# C12_1_0.net
KiCad netlist of a schematic drawn in EAGLE
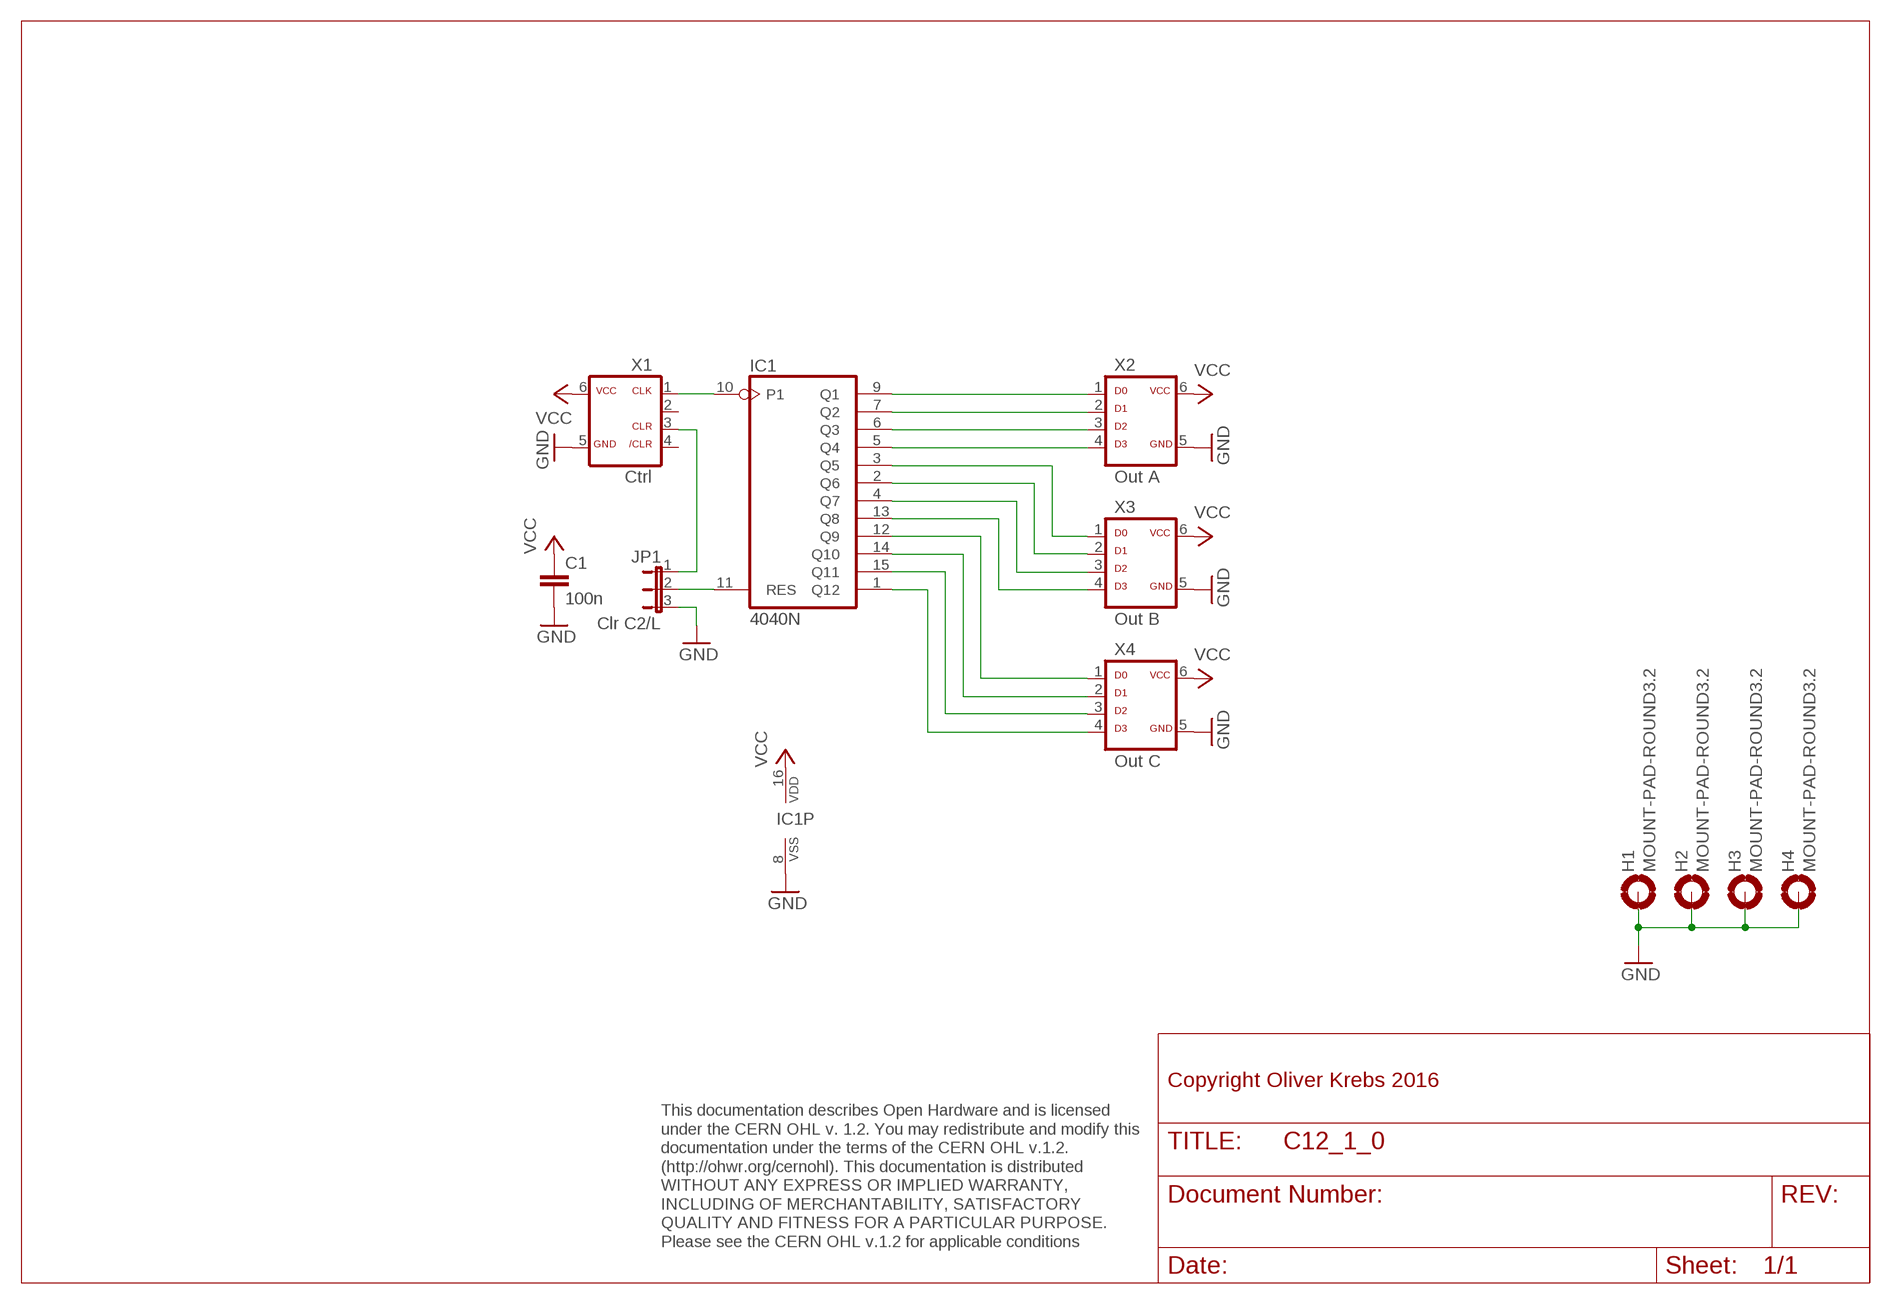
[diagram p0: schematic, sheet 1]

(export (version "E")
  (design (tool "Eeschema 10.0.6"))
  (components
    (comp (ref "C1")
      (value "100n")
      (footprint "eagle-import:C050-025X075")
      (libsource (lib "eagle-import") (part "C-EU050-025X075"))
    )
    (comp (ref "H1")
      (value "MOUNT-PAD-ROUND3.2")
      (footprint "eagle-import:3,2-PAD")
      (libsource (lib "eagle-import") (part "MOUNT-PAD-ROUND3.2"))
    )
    (comp (ref "H2")
      (value "MOUNT-PAD-ROUND3.2")
      (footprint "eagle-import:3,2-PAD")
      (libsource (lib "eagle-import") (part "MOUNT-PAD-ROUND3.2"))
    )
    (comp (ref "H3")
      (value "MOUNT-PAD-ROUND3.2")
      (footprint "eagle-import:3,2-PAD")
      (libsource (lib "eagle-import") (part "MOUNT-PAD-ROUND3.2"))
    )
    (comp (ref "H4")
      (value "MOUNT-PAD-ROUND3.2")
      (footprint "eagle-import:3,2-PAD")
      (libsource (lib "eagle-import") (part "MOUNT-PAD-ROUND3.2"))
    )
    (comp (ref "IC1")
      (value "4040N")
      (footprint "eagle-import:DIL16")
      (libsource (lib "eagle-import") (part "4040N"))
    )
    (comp (ref "JP1")
      (value "Clr C2/L")
      (footprint "eagle-import:JP2")
      (libsource (lib "eagle-import") (part "JP2E"))
    )
    (comp (ref "X1")
      (value "Ctrl")
      (footprint "eagle-import:ML-6")
      (libsource (lib "eagle-import") (part "ML6C"))
    )
    (comp (ref "X2")
      (value "Out A")
      (footprint "eagle-import:ML-6")
      (libsource (lib "eagle-import") (part "ML6D"))
    )
    (comp (ref "X3")
      (value "Out B")
      (footprint "eagle-import:ML-6")
      (libsource (lib "eagle-import") (part "ML6D"))
    )
    (comp (ref "X4")
      (value "Out C")
      (footprint "eagle-import:ML-6")
      (libsource (lib "eagle-import") (part "ML6D"))
    )
  )
  (nets
    (net (code "1") (name "GND") (class "Default")
      (node (ref "C1") (pin "2") (pinfunction "2_2") (pintype "passive"))
      (node (ref "H1") (pin "B3,2") (pinfunction "MOUNT_B3,2") (pintype "passive"))
      (node (ref "H2") (pin "B3,2") (pinfunction "MOUNT_B3,2") (pintype "passive"))
      (node (ref "H3") (pin "B3,2") (pinfunction "MOUNT_B3,2") (pintype "passive"))
      (node (ref "H4") (pin "B3,2") (pinfunction "MOUNT_B3,2") (pintype "passive"))
      (node (ref "IC1") (pin "8") (pinfunction "VSS_8") (pintype "power_in"))
      (node (ref "JP1") (pin "3") (pinfunction "3_3") (pintype "passive"))
      (node (ref "X1") (pin "5") (pinfunction "5_5") (pintype "passive"))
      (node (ref "X2") (pin "5") (pinfunction "5_5") (pintype "passive"))
      (node (ref "X3") (pin "5") (pinfunction "5_5") (pintype "passive"))
      (node (ref "X4") (pin "5") (pinfunction "5_5") (pintype "passive"))
    )
    (net (code "2") (name "Net-(IC1A-P1)") (class "Default")
      (node (ref "IC1") (pin "10") (pinfunction "P1_10") (pintype "input"))
      (node (ref "X1") (pin "1") (pinfunction "1_1") (pintype "passive"))
    )
    (net (code "3") (name "Net-(IC1A-Q1)") (class "Default")
      (node (ref "IC1") (pin "9") (pinfunction "Q1_9") (pintype "output"))
      (node (ref "X2") (pin "1") (pinfunction "1_1") (pintype "passive"))
    )
    (net (code "4") (name "Net-(IC1A-Q2)") (class "Default")
      (node (ref "IC1") (pin "7") (pinfunction "Q2_7") (pintype "output"))
      (node (ref "X2") (pin "2") (pinfunction "2_2") (pintype "passive"))
    )
    (net (code "5") (name "Net-(IC1A-Q3)") (class "Default")
      (node (ref "IC1") (pin "6") (pinfunction "Q3_6") (pintype "output"))
      (node (ref "X2") (pin "3") (pinfunction "3_3") (pintype "passive"))
    )
    (net (code "6") (name "Net-(IC1A-Q4)") (class "Default")
      (node (ref "IC1") (pin "5") (pinfunction "Q4_5") (pintype "output"))
      (node (ref "X2") (pin "4") (pinfunction "4_4") (pintype "passive"))
    )
    (net (code "7") (name "Net-(IC1A-Q5)") (class "Default")
      (node (ref "IC1") (pin "3") (pinfunction "Q5_3") (pintype "output"))
      (node (ref "X3") (pin "1") (pinfunction "1_1") (pintype "passive"))
    )
    (net (code "8") (name "Net-(IC1A-Q6)") (class "Default")
      (node (ref "IC1") (pin "2") (pinfunction "Q6_2") (pintype "output"))
      (node (ref "X3") (pin "2") (pinfunction "2_2") (pintype "passive"))
    )
    (net (code "9") (name "Net-(IC1A-Q7)") (class "Default")
      (node (ref "IC1") (pin "4") (pinfunction "Q7_4") (pintype "output"))
      (node (ref "X3") (pin "3") (pinfunction "3_3") (pintype "passive"))
    )
    (net (code "10") (name "Net-(IC1A-Q8)") (class "Default")
      (node (ref "IC1") (pin "13") (pinfunction "Q8_13") (pintype "output"))
      (node (ref "X3") (pin "4") (pinfunction "4_4") (pintype "passive"))
    )
    (net (code "11") (name "Net-(IC1A-Q9)") (class "Default")
      (node (ref "IC1") (pin "12") (pinfunction "Q9_12") (pintype "output"))
      (node (ref "X4") (pin "1") (pinfunction "1_1") (pintype "passive"))
    )
    (net (code "12") (name "Net-(IC1A-Q10)") (class "Default")
      (node (ref "IC1") (pin "14") (pinfunction "Q10_14") (pintype "output"))
      (node (ref "X4") (pin "2") (pinfunction "2_2") (pintype "passive"))
    )
    (net (code "13") (name "Net-(IC1A-Q11)") (class "Default")
      (node (ref "IC1") (pin "15") (pinfunction "Q11_15") (pintype "output"))
      (node (ref "X4") (pin "3") (pinfunction "3_3") (pintype "passive"))
    )
    (net (code "14") (name "Net-(IC1A-Q12)") (class "Default")
      (node (ref "IC1") (pin "1") (pinfunction "Q12_1") (pintype "output"))
      (node (ref "X4") (pin "4") (pinfunction "4_4") (pintype "passive"))
    )
    (net (code "15") (name "Net-(IC1A-RES)") (class "Default")
      (node (ref "IC1") (pin "11") (pinfunction "RES_11") (pintype "input"))
      (node (ref "JP1") (pin "2") (pinfunction "2_2") (pintype "passive"))
    )
    (net (code "16") (name "Net-(JP1-Pad1)") (class "Default")
      (node (ref "JP1") (pin "1") (pinfunction "1_1") (pintype "passive"))
      (node (ref "X1") (pin "3") (pinfunction "3_3") (pintype "passive"))
    )
    (net (code "17") (name "VCC") (class "Default")
      (node (ref "C1") (pin "1") (pinfunction "1_1") (pintype "passive"))
      (node (ref "IC1") (pin "16") (pinfunction "VDD_16") (pintype "power_in"))
      (node (ref "X1") (pin "6") (pinfunction "6_6") (pintype "passive"))
      (node (ref "X2") (pin "6") (pinfunction "6_6") (pintype "passive"))
      (node (ref "X3") (pin "6") (pinfunction "6_6") (pintype "passive"))
      (node (ref "X4") (pin "6") (pinfunction "6_6") (pintype "passive"))
    )
    (net (code "18") (name "unconnected-(X1-Pad2)") (class "Default")
      (node (ref "X1") (pin "2") (pinfunction "2_2") (pintype "passive"))
    )
    (net (code "19") (name "unconnected-(X1-Pad4)") (class "Default")
      (node (ref "X1") (pin "4") (pinfunction "4_4") (pintype "passive"))
    )
  )
)
